# aio_conn.net
KiCad netlist of a schematic drawn in Altium Designer
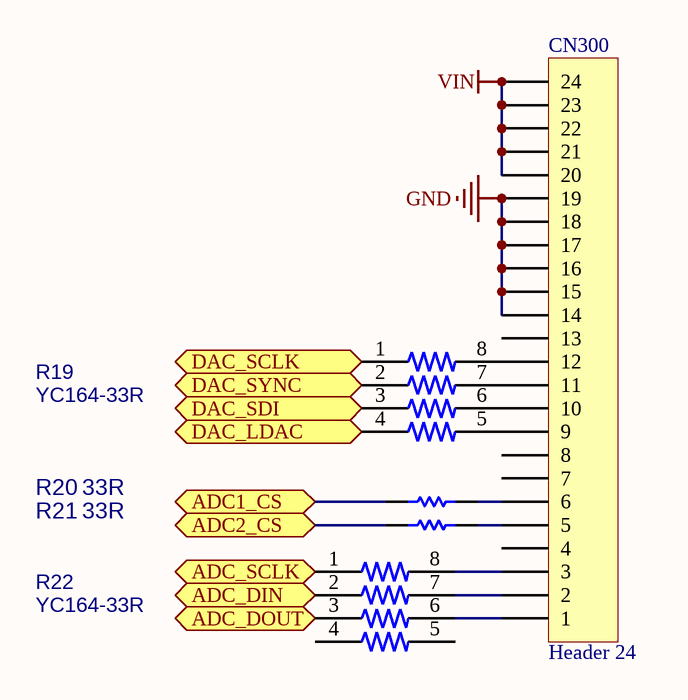
[diagram p0: aio_conn.SchDoc]

(export (version "E")
  (design (tool "Eeschema 10.0.6"))
  (components
    (comp (ref "CN300")
      (value "Header 24")
      (footprint "FPC-0.5-24")
      (description "Header, 24-Pin")
      (fields (field (name "PUBLISHER") "Altium Limited"))
      (libsource (lib "Miscellaneous Connectors") (part "Header 24"))
    )
    (comp (ref "R19")
      (value "YC164-33R")
      (footprint "YC164")
      (libsource (lib "PowerComps-more") (part "YC164"))
    )
    (comp (ref "R20")
      (value "33R")
      (footprint "R0603")
      (description "Resistor")
      (fields (field (name "PUBLISHER") "Altium Limited"))
      (libsource (lib "Miscellaneous Devices") (part "Res1"))
    )
    (comp (ref "R21")
      (value "33R")
      (footprint "R0603")
      (description "Resistor")
      (fields (field (name "PUBLISHER") "Altium Limited"))
      (libsource (lib "Miscellaneous Devices") (part "Res1"))
    )
    (comp (ref "R22")
      (value "YC164-33R")
      (footprint "YC164")
      (libsource (lib "PowerComps-more") (part "YC164"))
    )
  )
  (nets
    (net (code "1") (name "/ADC1_CS") (class "Default")
      (node (ref "R20") (pin "2") (pinfunction "2_2") (pintype "passive"))
    )
    (net (code "2") (name "/ADC2_CS") (class "Default")
      (node (ref "R21") (pin "2") (pinfunction "2_2") (pintype "passive"))
    )
    (net (code "3") (name "/ADC_DIN") (class "Default")
      (node (ref "R22") (pin "2") (pinfunction "2_2") (pintype "passive"))
    )
    (net (code "4") (name "/ADC_DOUT") (class "Default")
      (node (ref "R22") (pin "3") (pinfunction "3_3") (pintype "passive"))
    )
    (net (code "5") (name "/ADC_SCLK") (class "Default")
      (node (ref "R22") (pin "1") (pinfunction "1_1") (pintype "passive"))
    )
    (net (code "6") (name "/DAC_LDAC") (class "Default")
      (node (ref "R19") (pin "4") (pinfunction "4_4") (pintype "passive"))
    )
    (net (code "7") (name "/DAC_SCLK") (class "Default")
      (node (ref "R19") (pin "1") (pinfunction "1_1") (pintype "passive"))
    )
    (net (code "8") (name "/DAC_SDI") (class "Default")
      (node (ref "R19") (pin "3") (pinfunction "3_3") (pintype "passive"))
    )
    (net (code "9") (name "/DAC_SYNC") (class "Default")
      (node (ref "R19") (pin "2") (pinfunction "2_2") (pintype "passive"))
    )
    (net (code "10") (name "GND") (class "Default")
      (node (ref "CN300") (pin "14") (pinfunction "14_14") (pintype "passive"))
      (node (ref "CN300") (pin "15") (pinfunction "15_15") (pintype "passive"))
      (node (ref "CN300") (pin "16") (pinfunction "16_16") (pintype "passive"))
      (node (ref "CN300") (pin "17") (pinfunction "17_17") (pintype "passive"))
      (node (ref "CN300") (pin "18") (pinfunction "18_18") (pintype "passive"))
      (node (ref "CN300") (pin "19") (pinfunction "19_19") (pintype "passive"))
    )
    (net (code "11") (name "Net-(CN300-Pad1)") (class "Default")
      (node (ref "CN300") (pin "1") (pinfunction "1_1") (pintype "passive"))
      (node (ref "R22") (pin "6") (pinfunction "6_6") (pintype "passive"))
    )
    (net (code "12") (name "Net-(CN300-Pad2)") (class "Default")
      (node (ref "CN300") (pin "2") (pinfunction "2_2") (pintype "passive"))
      (node (ref "R22") (pin "7") (pinfunction "7_7") (pintype "passive"))
    )
    (net (code "13") (name "Net-(CN300-Pad3)") (class "Default")
      (node (ref "CN300") (pin "3") (pinfunction "3_3") (pintype "passive"))
      (node (ref "R22") (pin "8") (pinfunction "8_8") (pintype "passive"))
    )
    (net (code "14") (name "Net-(CN300-Pad5)") (class "Default")
      (node (ref "CN300") (pin "5") (pinfunction "5_5") (pintype "passive"))
      (node (ref "R21") (pin "1") (pinfunction "1_1") (pintype "passive"))
    )
    (net (code "15") (name "Net-(CN300-Pad6)") (class "Default")
      (node (ref "CN300") (pin "6") (pinfunction "6_6") (pintype "passive"))
      (node (ref "R20") (pin "1") (pinfunction "1_1") (pintype "passive"))
    )
    (net (code "16") (name "Net-(CN300-Pad9)") (class "Default")
      (node (ref "CN300") (pin "9") (pinfunction "9_9") (pintype "passive"))
      (node (ref "R19") (pin "5") (pinfunction "5_5") (pintype "passive"))
    )
    (net (code "17") (name "Net-(CN300-Pad10)") (class "Default")
      (node (ref "CN300") (pin "10") (pinfunction "10_10") (pintype "passive"))
      (node (ref "R19") (pin "6") (pinfunction "6_6") (pintype "passive"))
    )
    (net (code "18") (name "Net-(CN300-Pad11)") (class "Default")
      (node (ref "CN300") (pin "11") (pinfunction "11_11") (pintype "passive"))
      (node (ref "R19") (pin "7") (pinfunction "7_7") (pintype "passive"))
    )
    (net (code "19") (name "Net-(CN300-Pad12)") (class "Default")
      (node (ref "CN300") (pin "12") (pinfunction "12_12") (pintype "passive"))
      (node (ref "R19") (pin "8") (pinfunction "8_8") (pintype "passive"))
    )
    (net (code "20") (name "VIN") (class "Default")
      (node (ref "CN300") (pin "20") (pinfunction "20_20") (pintype "passive"))
      (node (ref "CN300") (pin "21") (pinfunction "21_21") (pintype "passive"))
      (node (ref "CN300") (pin "22") (pinfunction "22_22") (pintype "passive"))
      (node (ref "CN300") (pin "23") (pinfunction "23_23") (pintype "passive"))
      (node (ref "CN300") (pin "24") (pinfunction "24_24") (pintype "passive"))
    )
    (net (code "21") (name "unconnected-(CN300-Pad4)") (class "Default")
      (node (ref "CN300") (pin "4") (pinfunction "4_4") (pintype "passive"))
    )
    (net (code "22") (name "unconnected-(CN300-Pad7)") (class "Default")
      (node (ref "CN300") (pin "7") (pinfunction "7_7") (pintype "passive"))
    )
    (net (code "23") (name "unconnected-(CN300-Pad8)") (class "Default")
      (node (ref "CN300") (pin "8") (pinfunction "8_8") (pintype "passive"))
    )
    (net (code "24") (name "unconnected-(CN300-Pad13)") (class "Default")
      (node (ref "CN300") (pin "13") (pinfunction "13_13") (pintype "passive"))
    )
    (net (code "25") (name "unconnected-(R22-Pad4)") (class "Default")
      (node (ref "R22") (pin "4") (pinfunction "4_4") (pintype "passive"))
    )
    (net (code "26") (name "unconnected-(R22-Pad5)") (class "Default")
      (node (ref "R22") (pin "5") (pinfunction "5_5") (pintype "passive"))
    )
  )
)
